# Adafruit_ItsyBitsy_RP2040.net
KiCad netlist of a schematic drawn in EAGLE
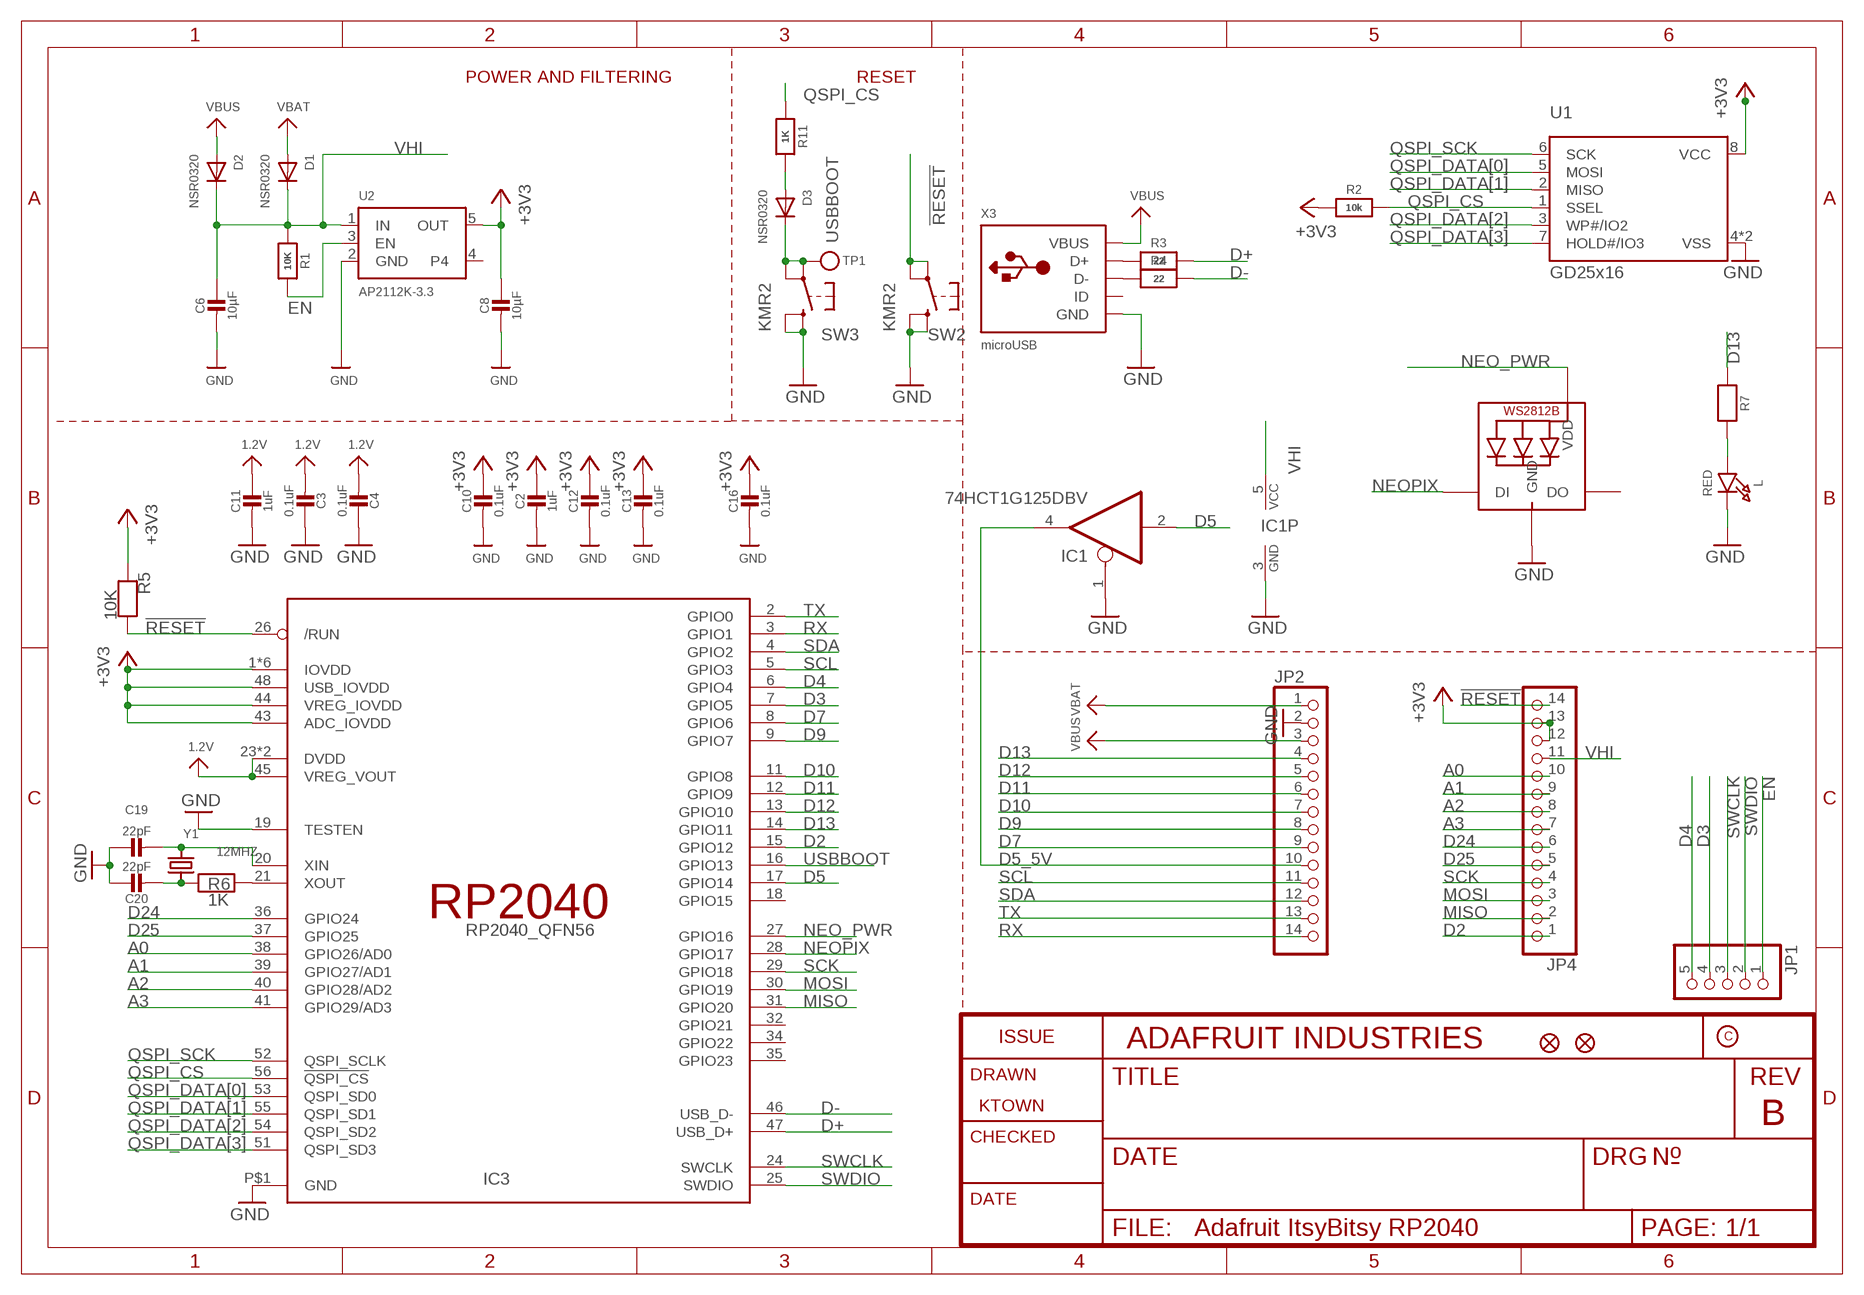
[diagram p0: schematic, sheet 1]

(export (version "E")
  (design (tool "Eeschema 10.0.6"))
  (components
    (comp (ref "C2")
      (value "1uF")
      (footprint "eagle-import:_0603MP")
      (libsource (lib "eagle-import") (part "CAP_CERAMIC_0603MP"))
    )
    (comp (ref "C3")
      (value "0.1uF")
      (footprint "eagle-import:_0402NO")
      (libsource (lib "eagle-import") (part "CAP_CERAMIC_0402NO"))
    )
    (comp (ref "C4")
      (value "0.1uF")
      (footprint "eagle-import:_0402NO")
      (libsource (lib "eagle-import") (part "CAP_CERAMIC_0402NO"))
    )
    (comp (ref "C6")
      (value "10µF")
      (footprint "eagle-import:0805-NO")
      (libsource (lib "eagle-import") (part "CAP_CERAMIC0805-NOOUTLINE"))
    )
    (comp (ref "C8")
      (value "10µF")
      (footprint "eagle-import:0805-NO")
      (libsource (lib "eagle-import") (part "CAP_CERAMIC0805-NOOUTLINE"))
    )
    (comp (ref "C10")
      (value "0.1uF")
      (footprint "eagle-import:_0402NO")
      (libsource (lib "eagle-import") (part "CAP_CERAMIC_0402NO"))
    )
    (comp (ref "C11")
      (value "1uF")
      (footprint "eagle-import:_0603MP")
      (libsource (lib "eagle-import") (part "CAP_CERAMIC_0603MP"))
    )
    (comp (ref "C12")
      (value "0.1uF")
      (footprint "eagle-import:_0402NO")
      (libsource (lib "eagle-import") (part "CAP_CERAMIC_0402NO"))
    )
    (comp (ref "C13")
      (value "0.1uF")
      (footprint "eagle-import:_0402NO")
      (libsource (lib "eagle-import") (part "CAP_CERAMIC_0402NO"))
    )
    (comp (ref "C16")
      (value "0.1uF")
      (footprint "eagle-import:_0402NO")
      (libsource (lib "eagle-import") (part "CAP_CERAMIC_0402NO"))
    )
    (comp (ref "C19")
      (value "22pF")
      (footprint "eagle-import:_0402NO")
      (libsource (lib "eagle-import") (part "CAP_CERAMIC_0402NO"))
    )
    (comp (ref "C20")
      (value "22pF")
      (footprint "eagle-import:_0402NO")
      (libsource (lib "eagle-import") (part "CAP_CERAMIC_0402NO"))
    )
    (comp (ref "D1")
      (value "NSR0320")
      (footprint "eagle-import:SOD-323F")
      (libsource (lib "eagle-import") (part "DIODESOD-323F"))
    )
    (comp (ref "D2")
      (value "NSR0320")
      (footprint "eagle-import:SOD-323F")
      (libsource (lib "eagle-import") (part "DIODESOD-323F"))
    )
    (comp (ref "D3")
      (value "NSR0320")
      (footprint "eagle-import:SOD-323F")
      (libsource (lib "eagle-import") (part "DIODESOD-323F"))
    )
    (comp (ref "IC1")
      (value "74HCT1G125DBV")
      (footprint "eagle-import:SC70-5")
      (libsource (lib "eagle-import") (part "741G125DCKAHC"))
    )
    (comp (ref "IC3")
      (value "RP2040_QFN56")
      (footprint "eagle-import:QFN56_7MM_REDUCEDEPAD")
      (libsource (lib "eagle-import") (part "RP2040_QFN56"))
    )
    (comp (ref "JP1")
      (value "HEADER-1X570MIL")
      (footprint "eagle-import:1X05_ROUND_70")
      (libsource (lib "eagle-import") (part "HEADER-1X570MIL"))
    )
    (comp (ref "JP2")
      (value "HEADER-1X14")
      (footprint "eagle-import:1X14_ROUND70")
      (libsource (lib "eagle-import") (part "HEADER-1X14"))
    )
    (comp (ref "JP4")
      (value "HEADER-1X14")
      (footprint "eagle-import:1X14_ROUND70")
      (libsource (lib "eagle-import") (part "HEADER-1X14"))
    )
    (comp (ref "L")
      (value "RED")
      (footprint "eagle-import:CHIPLED_0603_NOOUTLINE")
      (libsource (lib "eagle-import") (part "LED0603_NOOUTLINE"))
    )
    (comp (ref "LED1")
      (value "WS2812B_SK6805_1515")
      (footprint "eagle-import:SK6805_1515")
      (libsource (lib "eagle-import") (part "WS2812B_SK6805_1515"))
    )
    (comp (ref "R1")
      (value "10K")
      (footprint "eagle-import:_0402NO")
      (libsource (lib "eagle-import") (part "RESISTOR_0402NO"))
    )
    (comp (ref "R2")
      (value "10k")
      (footprint "eagle-import:_0402NO")
      (libsource (lib "eagle-import") (part "RESISTOR_0402NO"))
    )
    (comp (ref "R3")
      (value "22")
      (footprint "eagle-import:_0402NO")
      (libsource (lib "eagle-import") (part "RESISTOR_0402NO"))
    )
    (comp (ref "R4")
      (value "22")
      (footprint "eagle-import:_0402NO")
      (libsource (lib "eagle-import") (part "RESISTOR_0402NO"))
    )
    (comp (ref "R5")
      (value "10K")
      (footprint "eagle-import:_0402NO")
      (libsource (lib "eagle-import") (part "RESISTOR_0402NO"))
    )
    (comp (ref "R6")
      (value "1K")
      (footprint "eagle-import:_0402NO")
      (libsource (lib "eagle-import") (part "RESISTOR_0402NO"))
    )
    (comp (ref "R7")
      (value "1K")
      (footprint "eagle-import:_0402NO")
      (libsource (lib "eagle-import") (part "RESISTOR_0402NO"))
    )
    (comp (ref "R11")
      (value "1K")
      (footprint "eagle-import:_0402NO")
      (libsource (lib "eagle-import") (part "RESISTOR_0402NO"))
    )
    (comp (ref "SW2")
      (value "KMR2")
      (footprint "eagle-import:BTN_KMR2_4.6X2.8")
      (libsource (lib "eagle-import") (part "SWITCH_TACT_SMT4.6X2.8"))
    )
    (comp (ref "SW3")
      (value "KMR2")
      (footprint "eagle-import:BTN_KMR2_4.6X2.8")
      (libsource (lib "eagle-import") (part "SWITCH_TACT_SMT4.6X2.8"))
    )
    (comp (ref "TP1")
      (value "TESTPOINTROUND1.5MMNO")
      (footprint "eagle-import:TESTPOINT_ROUND_1.5MM_NO")
      (libsource (lib "eagle-import") (part "TESTPOINTROUND1.5MMNO"))
    )
    (comp (ref "U$34")
      (value "FIDUCIAL_1MM")
      (footprint "eagle-import:FIDUCIAL_1MM")
      (libsource (lib "eagle-import") (part "FIDUCIAL_1MM"))
    )
    (comp (ref "U$35")
      (value "FIDUCIAL_1MM")
      (footprint "eagle-import:FIDUCIAL_1MM")
      (libsource (lib "eagle-import") (part "FIDUCIAL_1MM"))
    )
    (comp (ref "U1")
      (value "GD25x16")
      (footprint "eagle-import:USON8_4X4")
      (libsource (lib "eagle-import") (part "SPIFLASH_8PIN_4X4"))
    )
    (comp (ref "U2")
      (value "AP2112K-3.3")
      (footprint "eagle-import:SOT23-5")
      (libsource (lib "eagle-import") (part "VREG_SOT23-5"))
    )
    (comp (ref "X3")
      (value "microUSB")
      (footprint "eagle-import:4UCONN_20329_NARROW")
      (libsource (lib "eagle-import") (part "USB_MICRO_NARROW"))
    )
    (comp (ref "Y1")
      (value "12MHZ")
      (footprint "eagle-import:CRYSTAL_2.5X2")
      (libsource (lib "eagle-import") (part "CRYSTAL2.5X2.0"))
    )
  )
  (nets
    (net (code "1") (name "+3V3") (class "Default")
      (node (ref "C10") (pin "1") (pinfunction "1_1") (pintype "passive"))
      (node (ref "C12") (pin "1") (pinfunction "1_1") (pintype "passive"))
      (node (ref "C13") (pin "1") (pinfunction "1_1") (pintype "passive"))
      (node (ref "C16") (pin "1") (pinfunction "1_1") (pintype "passive"))
      (node (ref "C2") (pin "1") (pinfunction "1_1") (pintype "passive"))
      (node (ref "C8") (pin "1") (pinfunction "1_1") (pintype "passive"))
      (node (ref "IC3") (pin "1") (pinfunction "IOVDD_1") (pintype "power_in"))
      (node (ref "IC3") (pin "10") (pinfunction "IOVDD_10") (pintype "power_in"))
      (node (ref "IC3") (pin "22") (pinfunction "IOVDD_22") (pintype "power_in"))
      (node (ref "IC3") (pin "33") (pinfunction "IOVDD_33") (pintype "power_in"))
      (node (ref "IC3") (pin "42") (pinfunction "IOVDD_42") (pintype "power_in"))
      (node (ref "IC3") (pin "43") (pinfunction "ADC_IOVDD_43") (pintype "power_in"))
      (node (ref "IC3") (pin "44") (pinfunction "VREG_IOVDD_44") (pintype "power_in"))
      (node (ref "IC3") (pin "48") (pinfunction "USB_IOVDD_48") (pintype "power_in"))
      (node (ref "IC3") (pin "49") (pinfunction "IOVDD_49") (pintype "power_in"))
      (node (ref "JP4") (pin "12") (pinfunction "12_12") (pintype "passive"))
      (node (ref "JP4") (pin "13") (pinfunction "13_13") (pintype "passive"))
      (node (ref "R2") (pin "1") (pinfunction "1_1") (pintype "passive"))
      (node (ref "R5") (pin "1") (pinfunction "1_1") (pintype "passive"))
      (node (ref "U1") (pin "8") (pinfunction "VCC_8") (pintype "bidirectional"))
      (node (ref "U2") (pin "5") (pinfunction "OUT_5") (pintype "power_in"))
    )
    (net (code "2") (name "/A0") (class "Default")
      (node (ref "IC3") (pin "38") (pinfunction "GPIO26/AD0_38") (pintype "bidirectional"))
      (node (ref "JP4") (pin "10") (pinfunction "10_10") (pintype "passive"))
    )
    (net (code "3") (name "/A1") (class "Default")
      (node (ref "IC3") (pin "39") (pinfunction "GPIO27/AD1_39") (pintype "bidirectional"))
      (node (ref "JP4") (pin "9") (pinfunction "9_9") (pintype "passive"))
    )
    (net (code "4") (name "/A2") (class "Default")
      (node (ref "IC3") (pin "40") (pinfunction "GPIO28/AD2_40") (pintype "bidirectional"))
      (node (ref "JP4") (pin "8") (pinfunction "8_8") (pintype "passive"))
    )
    (net (code "5") (name "/A3") (class "Default")
      (node (ref "IC3") (pin "41") (pinfunction "GPIO29/AD3_41") (pintype "bidirectional"))
      (node (ref "JP4") (pin "7") (pinfunction "7_7") (pintype "passive"))
    )
    (net (code "6") (name "/D+") (class "Default")
      (node (ref "IC3") (pin "47") (pinfunction "USB_D+_47") (pintype "bidirectional"))
      (node (ref "R3") (pin "2") (pinfunction "2_2") (pintype "passive"))
    )
    (net (code "7") (name "/D-") (class "Default")
      (node (ref "IC3") (pin "46") (pinfunction "USB_D-_46") (pintype "bidirectional"))
      (node (ref "R4") (pin "2") (pinfunction "2_2") (pintype "passive"))
    )
    (net (code "8") (name "/D2") (class "Default")
      (node (ref "IC3") (pin "15") (pinfunction "GPIO12_15") (pintype "bidirectional"))
      (node (ref "JP4") (pin "1") (pinfunction "1_1") (pintype "passive"))
    )
    (net (code "9") (name "/D3") (class "Default")
      (node (ref "IC3") (pin "7") (pinfunction "GPIO5_7") (pintype "bidirectional"))
      (node (ref "JP1") (pin "4") (pinfunction "4_4") (pintype "passive"))
    )
    (net (code "10") (name "/D4") (class "Default")
      (node (ref "IC3") (pin "6") (pinfunction "GPIO4_6") (pintype "bidirectional"))
      (node (ref "JP1") (pin "5") (pinfunction "5_5") (pintype "passive"))
    )
    (net (code "11") (name "/D5") (class "Default")
      (node (ref "IC1") (pin "2") (pinfunction "I_2") (pintype "input"))
      (node (ref "IC3") (pin "17") (pinfunction "GPIO14_17") (pintype "bidirectional"))
    )
    (net (code "12") (name "/D5_5V") (class "Default")
      (node (ref "IC1") (pin "4") (pinfunction "O_4") (pintype "tri_state"))
      (node (ref "JP2") (pin "10") (pinfunction "10_10") (pintype "passive"))
    )
    (net (code "13") (name "/D7") (class "Default")
      (node (ref "IC3") (pin "8") (pinfunction "GPIO6_8") (pintype "bidirectional"))
      (node (ref "JP2") (pin "9") (pinfunction "9_9") (pintype "passive"))
    )
    (net (code "14") (name "/D9") (class "Default")
      (node (ref "IC3") (pin "9") (pinfunction "GPIO7_9") (pintype "bidirectional"))
      (node (ref "JP2") (pin "8") (pinfunction "8_8") (pintype "passive"))
    )
    (net (code "15") (name "/D10") (class "Default")
      (node (ref "IC3") (pin "11") (pinfunction "GPIO8_11") (pintype "bidirectional"))
      (node (ref "JP2") (pin "7") (pinfunction "7_7") (pintype "passive"))
    )
    (net (code "16") (name "/D11") (class "Default")
      (node (ref "IC3") (pin "12") (pinfunction "GPIO9_12") (pintype "bidirectional"))
      (node (ref "JP2") (pin "6") (pinfunction "6_6") (pintype "passive"))
    )
    (net (code "17") (name "/D12") (class "Default")
      (node (ref "IC3") (pin "13") (pinfunction "GPIO10_13") (pintype "bidirectional"))
      (node (ref "JP2") (pin "5") (pinfunction "5_5") (pintype "passive"))
    )
    (net (code "18") (name "/D13") (class "Default")
      (node (ref "IC3") (pin "14") (pinfunction "GPIO11_14") (pintype "bidirectional"))
      (node (ref "JP2") (pin "4") (pinfunction "4_4") (pintype "passive"))
      (node (ref "R7") (pin "1") (pinfunction "1_1") (pintype "passive"))
    )
    (net (code "19") (name "/D24") (class "Default")
      (node (ref "IC3") (pin "36") (pinfunction "GPIO24_36") (pintype "bidirectional"))
      (node (ref "JP4") (pin "6") (pinfunction "6_6") (pintype "passive"))
    )
    (net (code "20") (name "/D25") (class "Default")
      (node (ref "IC3") (pin "37") (pinfunction "GPIO25_37") (pintype "bidirectional"))
      (node (ref "JP4") (pin "5") (pinfunction "5_5") (pintype "passive"))
    )
    (net (code "21") (name "/EN") (class "Default")
      (node (ref "JP1") (pin "1") (pinfunction "1_1") (pintype "passive"))
      (node (ref "R1") (pin "2") (pinfunction "2_2") (pintype "passive"))
      (node (ref "U2") (pin "3") (pinfunction "EN_3") (pintype "input"))
    )
    (net (code "22") (name "/MISO") (class "Default")
      (node (ref "IC3") (pin "31") (pinfunction "GPIO20_31") (pintype "bidirectional"))
      (node (ref "JP4") (pin "2") (pinfunction "2_2") (pintype "passive"))
    )
    (net (code "23") (name "/MOSI") (class "Default")
      (node (ref "IC3") (pin "30") (pinfunction "GPIO19_30") (pintype "bidirectional"))
      (node (ref "JP4") (pin "3") (pinfunction "3_3") (pintype "passive"))
    )
    (net (code "24") (name "/NEOPIX") (class "Default")
      (node (ref "IC3") (pin "28") (pinfunction "GPIO17_28") (pintype "bidirectional"))
      (node (ref "LED1") (pin "1") (pinfunction "DI_1") (pintype "input"))
    )
    (net (code "25") (name "/NEO_PWR") (class "Default")
      (node (ref "IC3") (pin "27") (pinfunction "GPIO16_27") (pintype "bidirectional"))
      (node (ref "LED1") (pin "2") (pinfunction "VDD_2") (pintype "power_in"))
    )
    (net (code "26") (name "/QSPI_CS") (class "Default")
      (node (ref "IC3") (pin "56") (pinfunction "~{QSPI_CS}_56") (pintype "bidirectional"))
      (node (ref "R11") (pin "1") (pinfunction "1_1") (pintype "passive"))
      (node (ref "R2") (pin "2") (pinfunction "2_2") (pintype "passive"))
      (node (ref "U1") (pin "1") (pinfunction "SSEL_1") (pintype "bidirectional"))
    )
    (net (code "27") (name "/QSPI_DATA[0]") (class "Default")
      (node (ref "IC3") (pin "53") (pinfunction "QSPI_SD0_53") (pintype "bidirectional"))
      (node (ref "U1") (pin "5") (pinfunction "MOSI_5") (pintype "bidirectional"))
    )
    (net (code "28") (name "/QSPI_DATA[1]") (class "Default")
      (node (ref "IC3") (pin "55") (pinfunction "QSPI_SD1_55") (pintype "bidirectional"))
      (node (ref "U1") (pin "2") (pinfunction "MISO_2") (pintype "bidirectional"))
    )
    (net (code "29") (name "/QSPI_DATA[2]") (class "Default")
      (node (ref "IC3") (pin "54") (pinfunction "QSPI_SD2_54") (pintype "bidirectional"))
      (node (ref "U1") (pin "3") (pinfunction "WP#/IO2_3") (pintype "bidirectional"))
    )
    (net (code "30") (name "/QSPI_DATA[3]") (class "Default")
      (node (ref "IC3") (pin "51") (pinfunction "QSPI_SD3_51") (pintype "bidirectional"))
      (node (ref "U1") (pin "7") (pinfunction "HOLD#/IO3_7") (pintype "bidirectional"))
    )
    (net (code "31") (name "/QSPI_SCK") (class "Default")
      (node (ref "IC3") (pin "52") (pinfunction "QSPI_SCLK_52") (pintype "bidirectional"))
      (node (ref "U1") (pin "6") (pinfunction "SCK_6") (pintype "bidirectional"))
    )
    (net (code "32") (name "/RX") (class "Default")
      (node (ref "IC3") (pin "3") (pinfunction "GPIO1_3") (pintype "bidirectional"))
      (node (ref "JP2") (pin "14") (pinfunction "14_14") (pintype "passive"))
    )
    (net (code "33") (name "/SCK") (class "Default")
      (node (ref "IC3") (pin "29") (pinfunction "GPIO18_29") (pintype "bidirectional"))
      (node (ref "JP4") (pin "4") (pinfunction "4_4") (pintype "passive"))
    )
    (net (code "34") (name "/SCL") (class "Default")
      (node (ref "IC3") (pin "5") (pinfunction "GPIO3_5") (pintype "bidirectional"))
      (node (ref "JP2") (pin "11") (pinfunction "11_11") (pintype "passive"))
    )
    (net (code "35") (name "/SDA") (class "Default")
      (node (ref "IC3") (pin "4") (pinfunction "GPIO2_4") (pintype "bidirectional"))
      (node (ref "JP2") (pin "12") (pinfunction "12_12") (pintype "passive"))
    )
    (net (code "36") (name "/SWCLK") (class "Default")
      (node (ref "IC3") (pin "24") (pinfunction "SWCLK_24") (pintype "bidirectional"))
      (node (ref "JP1") (pin "3") (pinfunction "3_3") (pintype "passive"))
    )
    (net (code "37") (name "/SWDIO") (class "Default")
      (node (ref "IC3") (pin "25") (pinfunction "SWDIO_25") (pintype "bidirectional"))
      (node (ref "JP1") (pin "2") (pinfunction "2_2") (pintype "passive"))
    )
    (net (code "38") (name "/TX") (class "Default")
      (node (ref "IC3") (pin "2") (pinfunction "GPIO0_2") (pintype "bidirectional"))
      (node (ref "JP2") (pin "13") (pinfunction "13_13") (pintype "passive"))
    )
    (net (code "39") (name "/USBBOOT") (class "Default")
      (node (ref "D3") (pin "C") (pinfunction "C_C") (pintype "passive"))
      (node (ref "IC3") (pin "16") (pinfunction "GPIO13_16") (pintype "bidirectional"))
      (node (ref "SW3") (pin "A") (pinfunction "P_A") (pintype "passive"))
      (node (ref "SW3") (pin "A'") (pinfunction "P1_A'") (pintype "passive"))
      (node (ref "TP1") (pin "P$1") (pinfunction "P$1_P$1") (pintype "bidirectional"))
    )
    (net (code "40") (name "/VHI") (class "Default")
      (node (ref "C6") (pin "1") (pinfunction "1_1") (pintype "passive"))
      (node (ref "D1") (pin "C") (pinfunction "C_C") (pintype "passive"))
      (node (ref "D2") (pin "C") (pinfunction "C_C") (pintype "passive"))
      (node (ref "IC1") (pin "5") (pinfunction "VCC_5") (pintype "power_in"))
      (node (ref "JP4") (pin "11") (pinfunction "11_11") (pintype "passive"))
      (node (ref "R1") (pin "1") (pinfunction "1_1") (pintype "passive"))
      (node (ref "U2") (pin "1") (pinfunction "IN_1") (pintype "power_in"))
    )
    (net (code "41") (name "/~{RESET}") (class "Default")
      (node (ref "IC3") (pin "26") (pinfunction "/RUN_26") (pintype "bidirectional"))
      (node (ref "JP4") (pin "14") (pinfunction "14_14") (pintype "passive"))
      (node (ref "R5") (pin "2") (pinfunction "2_2") (pintype "passive"))
      (node (ref "SW2") (pin "A") (pinfunction "P_A") (pintype "passive"))
      (node (ref "SW2") (pin "A'") (pinfunction "P1_A'") (pintype "passive"))
    )
    (net (code "42") (name "1.2V") (class "Default")
      (node (ref "C11") (pin "1") (pinfunction "1_1") (pintype "passive"))
      (node (ref "C3") (pin "2") (pinfunction "2_2") (pintype "passive"))
      (node (ref "C4") (pin "2") (pinfunction "2_2") (pintype "passive"))
      (node (ref "IC3") (pin "23") (pinfunction "DVDD_23") (pintype "power_in"))
      (node (ref "IC3") (pin "45") (pinfunction "VREG_VOUT_45") (pintype "power_in"))
      (node (ref "IC3") (pin "50") (pinfunction "DVDD_50") (pintype "power_in"))
    )
    (net (code "43") (name "GND") (class "Default")
      (node (ref "C10") (pin "2") (pinfunction "2_2") (pintype "passive"))
      (node (ref "C11") (pin "2") (pinfunction "2_2") (pintype "passive"))
      (node (ref "C12") (pin "2") (pinfunction "2_2") (pintype "passive"))
      (node (ref "C13") (pin "2") (pinfunction "2_2") (pintype "passive"))
      (node (ref "C16") (pin "2") (pinfunction "2_2") (pintype "passive"))
      (node (ref "C19") (pin "1") (pinfunction "1_1") (pintype "passive"))
      (node (ref "C2") (pin "2") (pinfunction "2_2") (pintype "passive"))
      (node (ref "C20") (pin "1") (pinfunction "1_1") (pintype "passive"))
      (node (ref "C3") (pin "1") (pinfunction "1_1") (pintype "passive"))
      (node (ref "C4") (pin "1") (pinfunction "1_1") (pintype "passive"))
      (node (ref "C6") (pin "2") (pinfunction "2_2") (pintype "passive"))
      (node (ref "C8") (pin "2") (pinfunction "2_2") (pintype "passive"))
      (node (ref "IC1") (pin "1") (pinfunction "OE_1") (pintype "input"))
      (node (ref "IC1") (pin "3") (pinfunction "GND_3") (pintype "power_in"))
      (node (ref "IC3") (pin "19") (pinfunction "TESTEN_19") (pintype "input"))
      (node (ref "IC3") (pin "P$1") (pinfunction "GND_P$1") (pintype "power_in"))
      (node (ref "JP2") (pin "2") (pinfunction "2_2") (pintype "passive"))
      (node (ref "L") (pin "C") (pinfunction "C_C") (pintype "passive"))
      (node (ref "LED1") (pin "4") (pinfunction "GND_4") (pintype "power_in"))
      (node (ref "SW2") (pin "B") (pinfunction "S_B") (pintype "passive"))
      (node (ref "SW2") (pin "B'") (pinfunction "S1_B'") (pintype "passive"))
      (node (ref "SW3") (pin "B") (pinfunction "S_B") (pintype "passive"))
      (node (ref "SW3") (pin "B'") (pinfunction "S1_B'") (pintype "passive"))
      (node (ref "U1") (pin "4") (pinfunction "VSS_4") (pintype "bidirectional"))
      (node (ref "U1") (pin "PAD") (pinfunction "VSS_PAD") (pintype "bidirectional"))
      (node (ref "U2") (pin "2") (pinfunction "GND_2") (pintype "power_in"))
      (node (ref "X3") (pin "BASE@1") (pinfunction "GND_BASE@1") (pintype "power_in"))
      (node (ref "X3") (pin "BASE@2") (pinfunction "GND_BASE@2") (pintype "power_in"))
      (node (ref "X3") (pin "GND") (pinfunction "GND_GND") (pintype "power_in"))
      (node (ref "X3") (pin "SPRT@1") (pinfunction "GND_SPRT@1") (pintype "power_in"))
      (node (ref "X3") (pin "SPRT@2") (pinfunction "GND_SPRT@2") (pintype "power_in"))
      (node (ref "X3") (pin "SPRT@3") (pinfunction "GND_SPRT@3") (pintype "power_in"))
      (node (ref "X3") (pin "SPRT@4") (pinfunction "GND_SPRT@4") (pintype "power_in"))
    )
    (net (code "44") (name "Net-(C20-Pad2)") (class "Default")
      (node (ref "C20") (pin "2") (pinfunction "2_2") (pintype "passive"))
      (node (ref "R6") (pin "1") (pinfunction "1_1") (pintype "passive"))
      (node (ref "Y1") (pin "1") (pinfunction "1_1") (pintype "passive"))
    )
    (net (code "45") (name "Net-(D3-PadA)") (class "Default")
      (node (ref "D3") (pin "A") (pinfunction "A_A") (pintype "passive"))
      (node (ref "R11") (pin "2") (pinfunction "2_2") (pintype "passive"))
    )
    (net (code "46") (name "Net-(IC3-XIN)") (class "Default")
      (node (ref "C19") (pin "2") (pinfunction "2_2") (pintype "passive"))
      (node (ref "IC3") (pin "20") (pinfunction "XIN_20") (pintype "input"))
      (node (ref "Y1") (pin "3") (pinfunction "2_3") (pintype "passive"))
    )
    (net (code "47") (name "Net-(IC3-XOUT)") (class "Default")
      (node (ref "IC3") (pin "21") (pinfunction "XOUT_21") (pintype "output"))
      (node (ref "R6") (pin "2") (pinfunction "2_2") (pintype "passive"))
    )
    (net (code "48") (name "Net-(L-PadA)") (class "Default")
      (node (ref "L") (pin "A") (pinfunction "A_A") (pintype "passive"))
      (node (ref "R7") (pin "2") (pinfunction "2_2") (pintype "passive"))
    )
    (net (code "49") (name "Net-(R3-Pad1)") (class "Default")
      (node (ref "R3") (pin "1") (pinfunction "1_1") (pintype "passive"))
      (node (ref "X3") (pin "D+") (pinfunction "D+_D+") (pintype "bidirectional"))
    )
    (net (code "50") (name "Net-(R4-Pad1)") (class "Default")
      (node (ref "R4") (pin "1") (pinfunction "1_1") (pintype "passive"))
      (node (ref "X3") (pin "D-") (pinfunction "D-_D-") (pintype "bidirectional"))
    )
    (net (code "51") (name "VBAT") (class "Default")
      (node (ref "D1") (pin "A") (pinfunction "A_A") (pintype "passive"))
      (node (ref "JP2") (pin "1") (pinfunction "1_1") (pintype "passive"))
    )
    (net (code "52") (name "VBUS") (class "Default")
      (node (ref "D2") (pin "A") (pinfunction "A_A") (pintype "passive"))
      (node (ref "JP2") (pin "3") (pinfunction "3_3") (pintype "passive"))
      (node (ref "X3") (pin "VBUS") (pinfunction "VBUS_VBUS") (pintype "power_in"))
    )
    (net (code "53") (name "unconnected-(IC3-GPIO15-Pad18)") (class "Default")
      (node (ref "IC3") (pin "18") (pinfunction "GPIO15_18") (pintype "bidirectional"))
    )
    (net (code "54") (name "unconnected-(IC3-GPIO21-Pad32)") (class "Default")
      (node (ref "IC3") (pin "32") (pinfunction "GPIO21_32") (pintype "bidirectional"))
    )
    (net (code "55") (name "unconnected-(IC3-GPIO22-Pad34)") (class "Default")
      (node (ref "IC3") (pin "34") (pinfunction "GPIO22_34") (pintype "bidirectional"))
    )
    (net (code "56") (name "unconnected-(IC3-GPIO23-Pad35)") (class "Default")
      (node (ref "IC3") (pin "35") (pinfunction "GPIO23_35") (pintype "bidirectional"))
    )
    (net (code "57") (name "unconnected-(LED1-DO-Pad3)") (class "Default")
      (node (ref "LED1") (pin "3") (pinfunction "DO_3") (pintype "output"))
    )
    (net (code "58") (name "unconnected-(U2-P4-Pad4)") (class "Default")
      (node (ref "U2") (pin "4") (pinfunction "P4_4") (pintype "bidirectional"))
    )
    (net (code "59") (name "unconnected-(X3-PadID)") (class "Default")
      (node (ref "X3") (pin "ID") (pinfunction "ID_ID") (pintype "bidirectional"))
    )
  )
)
